# steady_mega_shield_v1_4.net
KiCad netlist of a schematic drawn in EAGLE
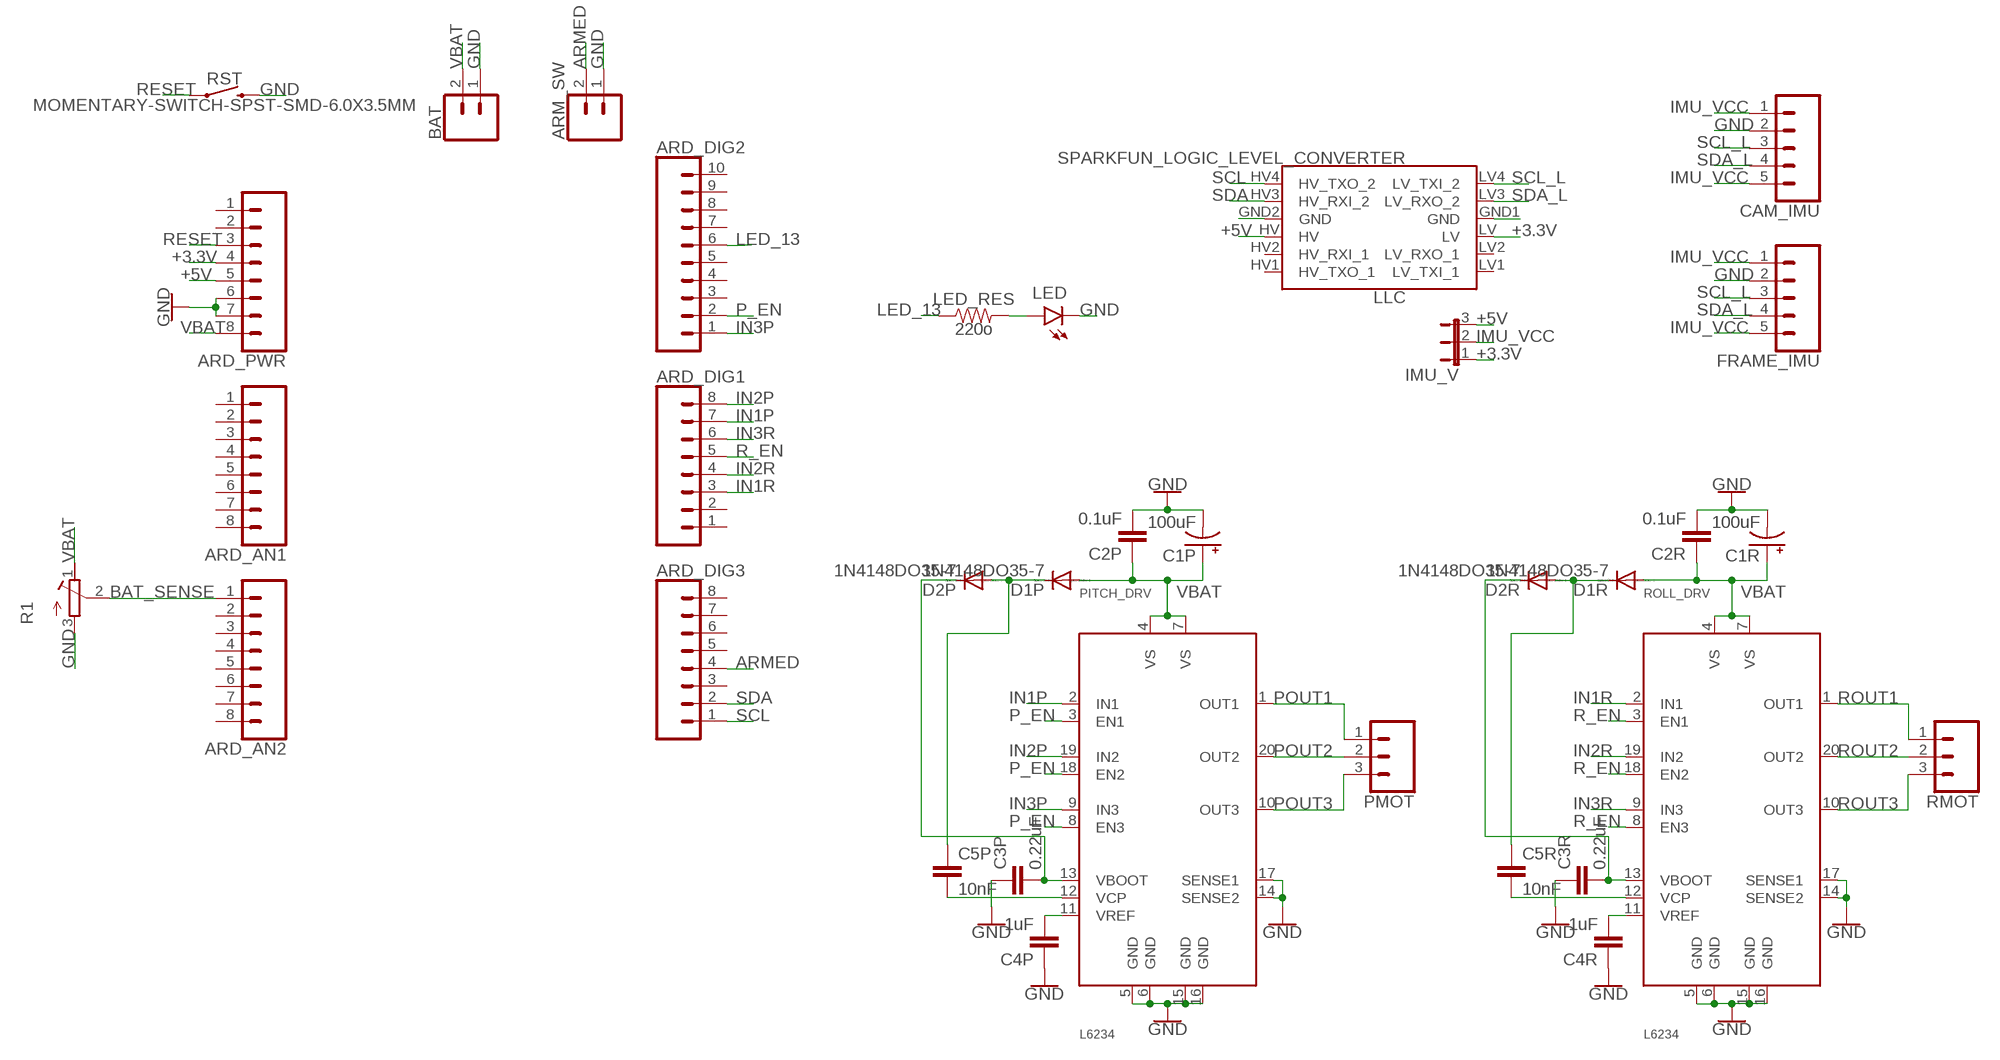
[diagram p0: schematic, sheet 1]

(export (version "E")
  (design (tool "Eeschema 10.0.6"))
  (components
    (comp (ref "ARD_AN1")
      (value "CONN_08\"")
      (footprint "eagle-import:1X08")
      (libsource (lib "eagle-import") (part "CONN_08{dblquote}"))
    )
    (comp (ref "ARD_AN2")
      (value "CONN_08\"")
      (footprint "eagle-import:1X08")
      (libsource (lib "eagle-import") (part "CONN_08{dblquote}"))
    )
    (comp (ref "ARD_DIG1")
      (value "CONN_08\"")
      (footprint "eagle-import:1X08")
      (libsource (lib "eagle-import") (part "CONN_08{dblquote}"))
    )
    (comp (ref "ARD_DIG2")
      (value "CONN_10\"")
      (footprint "eagle-import:1X10")
      (libsource (lib "eagle-import") (part "CONN_10{dblquote}"))
    )
    (comp (ref "ARD_DIG3")
      (value "CONN_08\"")
      (footprint "eagle-import:1X08")
      (libsource (lib "eagle-import") (part "CONN_08{dblquote}"))
    )
    (comp (ref "ARD_PWR")
      (value "CONN_08\"")
      (footprint "eagle-import:1X08")
      (libsource (lib "eagle-import") (part "CONN_08{dblquote}"))
    )
    (comp (ref "ARM_SW")
      (value "CONN_02")
      (footprint "eagle-import:1X02")
      (libsource (lib "eagle-import") (part "CONN_02"))
    )
    (comp (ref "BAT")
      (value "CONN_02")
      (footprint "eagle-import:1X02")
      (libsource (lib "eagle-import") (part "CONN_02"))
    )
    (comp (ref "C1P")
      (value "100uF")
      (footprint "eagle-import:CPOL-RADIAL-2.5MM-6.5MM")
      (libsource (lib "eagle-import") (part "100UF-POLAR-RADIAL-2.5MM-25V-20%"))
    )
    (comp (ref "C1R")
      (value "100uF")
      (footprint "eagle-import:CPOL-RADIAL-2.5MM-6.5MM")
      (libsource (lib "eagle-import") (part "100UF-POLAR-RADIAL-2.5MM-25V-20%"))
    )
    (comp (ref "C2P")
      (value "0.1uF")
      (footprint "eagle-import:C025-024X044")
      (libsource (lib "eagle-import") (part "C-EU025-024X044"))
    )
    (comp (ref "C2R")
      (value "0.1uF")
      (footprint "eagle-import:C025-024X044")
      (libsource (lib "eagle-import") (part "C-EU025-024X044"))
    )
    (comp (ref "C3P")
      (value "0.22uF")
      (footprint "eagle-import:C5B2.5")
      (libsource (lib "eagle-import") (part "C5/2.5"))
    )
    (comp (ref "C3R")
      (value "0.22uF")
      (footprint "eagle-import:C5B2.5")
      (libsource (lib "eagle-import") (part "C5/2.5"))
    )
    (comp (ref "C4P")
      (value "1uF")
      (footprint "eagle-import:C5B5.5")
      (libsource (lib "eagle-import") (part "C5/5.5"))
    )
    (comp (ref "C4R")
      (value "1uF")
      (footprint "eagle-import:C5B5.5")
      (libsource (lib "eagle-import") (part "C5/5.5"))
    )
    (comp (ref "C5P")
      (value "10nF")
      (footprint "eagle-import:C5B2.5")
      (libsource (lib "eagle-import") (part "C5/2.5"))
    )
    (comp (ref "C5R")
      (value "10nF")
      (footprint "eagle-import:C5B2.5")
      (libsource (lib "eagle-import") (part "C5/2.5"))
    )
    (comp (ref "CAM_IMU")
      (value "CONN_05JST")
      (footprint "eagle-import:JST-5-PTH")
      (libsource (lib "eagle-import") (part "CONN_05JST"))
    )
    (comp (ref "D1P")
      (value "1N4148DO35-7")
      (footprint "eagle-import:DO35-7")
      (libsource (lib "eagle-import") (part "1N4148DO35-7"))
    )
    (comp (ref "D1R")
      (value "1N4148DO35-7")
      (footprint "eagle-import:DO35-7")
      (libsource (lib "eagle-import") (part "1N4148DO35-7"))
    )
    (comp (ref "D2P")
      (value "1N4148DO35-7")
      (footprint "eagle-import:DO35-7")
      (libsource (lib "eagle-import") (part "1N4148DO35-7"))
    )
    (comp (ref "D2R")
      (value "1N4148DO35-7")
      (footprint "eagle-import:DO35-7")
      (libsource (lib "eagle-import") (part "1N4148DO35-7"))
    )
    (comp (ref "FRAME_IMU")
      (value "CONN_05JST")
      (footprint "eagle-import:JST-5-PTH")
      (libsource (lib "eagle-import") (part "CONN_05JST"))
    )
    (comp (ref "IMU_V")
      (value "JP2E")
      (footprint "eagle-import:JP2")
      (libsource (lib "eagle-import") (part "JP2E"))
    )
    (comp (ref "LED")
      (value "LED3MM")
      (footprint "eagle-import:LED_3MM")
      (libsource (lib "eagle-import") (part "LED3MM"))
    )
    (comp (ref "LED_RES")
      (value "220o")
      (footprint "eagle-import:0805")
      (libsource (lib "eagle-import") (part "RESISTOR0805"))
    )
    (comp (ref "LLC")
      (value "SPARKFUN_LOGIC_LEVEL_CONVERTER")
      (footprint "eagle-import:SPARKFUN_LOGIC_LEVEL_CONVERTER")
      (libsource (lib "eagle-import") (part "SPARKFUN_LOGIC_LEVEL_CONVERTER"))
    )
    (comp (ref "PITCH_DRV")
      (value "L6234")
      (footprint "eagle-import:DIL20")
      (libsource (lib "eagle-import") (part "L6234"))
    )
    (comp (ref "PMOT")
      (value "CONN_03POLAR")
      (footprint "eagle-import:MOLEX-1X3")
      (libsource (lib "eagle-import") (part "CONN_03POLAR"))
    )
    (comp (ref "R1")
      (value "R-TRIMMT93XB")
      (footprint "eagle-import:RTRIMT93XB")
      (libsource (lib "eagle-import") (part "R-TRIMMT93XB"))
    )
    (comp (ref "RMOT")
      (value "CONN_03POLAR")
      (footprint "eagle-import:MOLEX-1X3")
      (libsource (lib "eagle-import") (part "CONN_03POLAR"))
    )
    (comp (ref "ROLL_DRV")
      (value "L6234")
      (footprint "eagle-import:DIL20")
      (libsource (lib "eagle-import") (part "L6234"))
    )
    (comp (ref "RST")
      (value "MOMENTARY-SWITCH-SPST-SMD-6.0X3.5MM")
      (footprint "eagle-import:TACTILE_SWITCH_SMD_6.0X3.5MM")
      (libsource (lib "eagle-import") (part "MOMENTARY-SWITCH-SPST-SMD-6.0X3.5MM"))
    )
  )
  (nets
    (net (code "1") (name "/+3.3V") (class "Default")
      (node (ref "ARD_PWR") (pin "4") (pinfunction "4_4") (pintype "passive"))
      (node (ref "IMU_V") (pin "1") (pinfunction "1_1") (pintype "passive"))
      (node (ref "LLC") (pin "LV") (pinfunction "LV_LV") (pintype "power_in"))
    )
    (net (code "2") (name "/+5V") (class "Default")
      (node (ref "ARD_PWR") (pin "5") (pinfunction "5_5") (pintype "passive"))
      (node (ref "IMU_V") (pin "3") (pinfunction "3_3") (pintype "passive"))
      (node (ref "LLC") (pin "HV") (pinfunction "HV_HV") (pintype "power_in"))
    )
    (net (code "3") (name "/ARMED") (class "Default")
      (node (ref "ARD_DIG3") (pin "4") (pinfunction "4_4") (pintype "passive"))
      (node (ref "ARM_SW") (pin "2") (pinfunction "2_2") (pintype "passive"))
    )
    (net (code "4") (name "/BAT_SENSE") (class "Default")
      (node (ref "ARD_AN2") (pin "1") (pinfunction "1_1") (pintype "passive"))
      (node (ref "R1") (pin "2") (pinfunction "S_2") (pintype "passive"))
    )
    (net (code "5") (name "/IMU_VCC") (class "Default")
      (node (ref "CAM_IMU") (pin "1") (pinfunction "1_1") (pintype "passive"))
      (node (ref "CAM_IMU") (pin "5") (pinfunction "5_5") (pintype "passive"))
      (node (ref "FRAME_IMU") (pin "1") (pinfunction "1_1") (pintype "passive"))
      (node (ref "FRAME_IMU") (pin "5") (pinfunction "5_5") (pintype "passive"))
      (node (ref "IMU_V") (pin "2") (pinfunction "2_2") (pintype "passive"))
    )
    (net (code "6") (name "/IN1P") (class "Default")
      (node (ref "ARD_DIG1") (pin "7") (pinfunction "7_7") (pintype "passive"))
      (node (ref "PITCH_DRV") (pin "2") (pinfunction "IN1_2") (pintype "bidirectional"))
    )
    (net (code "7") (name "/IN1R") (class "Default")
      (node (ref "ARD_DIG1") (pin "3") (pinfunction "3_3") (pintype "passive"))
      (node (ref "ROLL_DRV") (pin "2") (pinfunction "IN1_2") (pintype "bidirectional"))
    )
    (net (code "8") (name "/IN2P") (class "Default")
      (node (ref "ARD_DIG1") (pin "8") (pinfunction "8_8") (pintype "passive"))
      (node (ref "PITCH_DRV") (pin "19") (pinfunction "IN2_19") (pintype "bidirectional"))
    )
    (net (code "9") (name "/IN2R") (class "Default")
      (node (ref "ARD_DIG1") (pin "4") (pinfunction "4_4") (pintype "passive"))
      (node (ref "ROLL_DRV") (pin "19") (pinfunction "IN2_19") (pintype "bidirectional"))
    )
    (net (code "10") (name "/IN3P") (class "Default")
      (node (ref "ARD_DIG2") (pin "1") (pinfunction "1_1") (pintype "passive"))
      (node (ref "PITCH_DRV") (pin "9") (pinfunction "IN3_9") (pintype "bidirectional"))
    )
    (net (code "11") (name "/IN3R") (class "Default")
      (node (ref "ARD_DIG1") (pin "6") (pinfunction "6_6") (pintype "passive"))
      (node (ref "ROLL_DRV") (pin "9") (pinfunction "IN3_9") (pintype "bidirectional"))
    )
    (net (code "12") (name "/LED_13") (class "Default")
      (node (ref "ARD_DIG2") (pin "6") (pinfunction "6_6") (pintype "passive"))
      (node (ref "LED_RES") (pin "1") (pinfunction "1_1") (pintype "passive"))
    )
    (net (code "13") (name "/POUT1") (class "Default")
      (node (ref "PITCH_DRV") (pin "1") (pinfunction "OUT1_1") (pintype "bidirectional"))
      (node (ref "PMOT") (pin "1") (pinfunction "1_1") (pintype "passive"))
    )
    (net (code "14") (name "/POUT2") (class "Default")
      (node (ref "PITCH_DRV") (pin "20") (pinfunction "OUT2_20") (pintype "bidirectional"))
      (node (ref "PMOT") (pin "2") (pinfunction "2_2") (pintype "passive"))
    )
    (net (code "15") (name "/POUT3") (class "Default")
      (node (ref "PITCH_DRV") (pin "10") (pinfunction "OUT3_10") (pintype "bidirectional"))
      (node (ref "PMOT") (pin "3") (pinfunction "3_3") (pintype "passive"))
    )
    (net (code "16") (name "/P_EN") (class "Default")
      (node (ref "ARD_DIG2") (pin "2") (pinfunction "2_2") (pintype "passive"))
      (node (ref "PITCH_DRV") (pin "18") (pinfunction "EN2_18") (pintype "bidirectional"))
      (node (ref "PITCH_DRV") (pin "3") (pinfunction "EN1_3") (pintype "bidirectional"))
      (node (ref "PITCH_DRV") (pin "8") (pinfunction "EN3_8") (pintype "bidirectional"))
    )
    (net (code "17") (name "/RESET") (class "Default")
      (node (ref "ARD_PWR") (pin "3") (pinfunction "3_3") (pintype "passive"))
      (node (ref "RST") (pin "1") (pinfunction "1_1") (pintype "passive"))
    )
    (net (code "18") (name "/ROUT1") (class "Default")
      (node (ref "RMOT") (pin "1") (pinfunction "1_1") (pintype "passive"))
      (node (ref "ROLL_DRV") (pin "1") (pinfunction "OUT1_1") (pintype "bidirectional"))
    )
    (net (code "19") (name "/ROUT2") (class "Default")
      (node (ref "RMOT") (pin "2") (pinfunction "2_2") (pintype "passive"))
      (node (ref "ROLL_DRV") (pin "20") (pinfunction "OUT2_20") (pintype "bidirectional"))
    )
    (net (code "20") (name "/ROUT3") (class "Default")
      (node (ref "RMOT") (pin "3") (pinfunction "3_3") (pintype "passive"))
      (node (ref "ROLL_DRV") (pin "10") (pinfunction "OUT3_10") (pintype "bidirectional"))
    )
    (net (code "21") (name "/R_EN") (class "Default")
      (node (ref "ARD_DIG1") (pin "5") (pinfunction "5_5") (pintype "passive"))
      (node (ref "ROLL_DRV") (pin "18") (pinfunction "EN2_18") (pintype "bidirectional"))
      (node (ref "ROLL_DRV") (pin "3") (pinfunction "EN1_3") (pintype "bidirectional"))
      (node (ref "ROLL_DRV") (pin "8") (pinfunction "EN3_8") (pintype "bidirectional"))
    )
    (net (code "22") (name "/SCL") (class "Default")
      (node (ref "ARD_DIG3") (pin "1") (pinfunction "1_1") (pintype "passive"))
      (node (ref "LLC") (pin "HV4") (pinfunction "HV_TXO_2_HV4") (pintype "bidirectional"))
    )
    (net (code "23") (name "/SCL_L") (class "Default")
      (node (ref "CAM_IMU") (pin "3") (pinfunction "3_3") (pintype "passive"))
      (node (ref "FRAME_IMU") (pin "3") (pinfunction "3_3") (pintype "passive"))
      (node (ref "LLC") (pin "LV4") (pinfunction "LV_TXI_2_LV4") (pintype "bidirectional"))
    )
    (net (code "24") (name "/SDA") (class "Default")
      (node (ref "ARD_DIG3") (pin "2") (pinfunction "2_2") (pintype "passive"))
      (node (ref "LLC") (pin "HV3") (pinfunction "HV_RXI_2_HV3") (pintype "bidirectional"))
    )
    (net (code "25") (name "/SDA_L") (class "Default")
      (node (ref "CAM_IMU") (pin "4") (pinfunction "4_4") (pintype "passive"))
      (node (ref "FRAME_IMU") (pin "4") (pinfunction "4_4") (pintype "passive"))
      (node (ref "LLC") (pin "LV3") (pinfunction "LV_RXO_2_LV3") (pintype "bidirectional"))
    )
    (net (code "26") (name "/VBAT") (class "Default")
      (node (ref "ARD_PWR") (pin "8") (pinfunction "8_8") (pintype "passive"))
      (node (ref "BAT") (pin "2") (pinfunction "2_2") (pintype "passive"))
      (node (ref "C1P") (pin "1") (pinfunction "+_1") (pintype "passive"))
      (node (ref "C1R") (pin "1") (pinfunction "+_1") (pintype "passive"))
      (node (ref "C2P") (pin "1") (pinfunction "1_1") (pintype "passive"))
      (node (ref "C2R") (pin "1") (pinfunction "1_1") (pintype "passive"))
      (node (ref "D1P") (pin "A") (pinfunction "A_A") (pintype "passive"))
      (node (ref "D1R") (pin "A") (pinfunction "A_A") (pintype "passive"))
      (node (ref "PITCH_DRV") (pin "4") (pinfunction "VS_4") (pintype "bidirectional"))
      (node (ref "PITCH_DRV") (pin "7") (pinfunction "VS_7") (pintype "bidirectional"))
      (node (ref "R1") (pin "1") (pinfunction "E_1") (pintype "passive"))
      (node (ref "ROLL_DRV") (pin "4") (pinfunction "VS_4") (pintype "bidirectional"))
      (node (ref "ROLL_DRV") (pin "7") (pinfunction "VS_7") (pintype "bidirectional"))
    )
    (net (code "27") (name "GND") (class "Default")
      (node (ref "ARD_PWR") (pin "6") (pinfunction "6_6") (pintype "passive"))
      (node (ref "ARD_PWR") (pin "7") (pinfunction "7_7") (pintype "passive"))
      (node (ref "ARM_SW") (pin "1") (pinfunction "1_1") (pintype "passive"))
      (node (ref "BAT") (pin "1") (pinfunction "1_1") (pintype "passive"))
      (node (ref "C1P") (pin "2") (pinfunction "-_2") (pintype "passive"))
      (node (ref "C1R") (pin "2") (pinfunction "-_2") (pintype "passive"))
      (node (ref "C2P") (pin "2") (pinfunction "2_2") (pintype "passive"))
      (node (ref "C2R") (pin "2") (pinfunction "2_2") (pintype "passive"))
      (node (ref "C3P") (pin "1") (pinfunction "1_1") (pintype "passive"))
      (node (ref "C3R") (pin "1") (pinfunction "1_1") (pintype "passive"))
      (node (ref "C4P") (pin "1") (pinfunction "1_1") (pintype "passive"))
      (node (ref "C4R") (pin "1") (pinfunction "1_1") (pintype "passive"))
      (node (ref "CAM_IMU") (pin "2") (pinfunction "2_2") (pintype "passive"))
      (node (ref "FRAME_IMU") (pin "2") (pinfunction "2_2") (pintype "passive"))
      (node (ref "LED") (pin "K") (pinfunction "C_K") (pintype "passive"))
      (node (ref "LLC") (pin "GND1") (pinfunction "GND_GND1") (pintype "power_in"))
      (node (ref "LLC") (pin "GND2") (pinfunction "GND_GND2") (pintype "power_in"))
      (node (ref "PITCH_DRV") (pin "14") (pinfunction "SENSE2_14") (pintype "bidirectional"))
      (node (ref "PITCH_DRV") (pin "15") (pinfunction "GND_15") (pintype "bidirectional"))
      (node (ref "PITCH_DRV") (pin "16") (pinfunction "GND_16") (pintype "bidirectional"))
      (node (ref "PITCH_DRV") (pin "17") (pinfunction "SENSE1_17") (pintype "bidirectional"))
      (node (ref "PITCH_DRV") (pin "5") (pinfunction "GND_5") (pintype "bidirectional"))
      (node (ref "PITCH_DRV") (pin "6") (pinfunction "GND_6") (pintype "bidirectional"))
      (node (ref "R1") (pin "3") (pinfunction "A_3") (pintype "passive"))
      (node (ref "ROLL_DRV") (pin "14") (pinfunction "SENSE2_14") (pintype "bidirectional"))
      (node (ref "ROLL_DRV") (pin "15") (pinfunction "GND_15") (pintype "bidirectional"))
      (node (ref "ROLL_DRV") (pin "16") (pinfunction "GND_16") (pintype "bidirectional"))
      (node (ref "ROLL_DRV") (pin "17") (pinfunction "SENSE1_17") (pintype "bidirectional"))
      (node (ref "ROLL_DRV") (pin "5") (pinfunction "GND_5") (pintype "bidirectional"))
      (node (ref "ROLL_DRV") (pin "6") (pinfunction "GND_6") (pintype "bidirectional"))
      (node (ref "RST") (pin "2") (pinfunction "2_2") (pintype "passive"))
    )
    (net (code "28") (name "Net-(C5P-Pad1)") (class "Default")
      (node (ref "C5P") (pin "1") (pinfunction "1_1") (pintype "passive"))
      (node (ref "D1P") (pin "C") (pinfunction "C_C") (pintype "passive"))
      (node (ref "D2P") (pin "A") (pinfunction "A_A") (pintype "passive"))
    )
    (net (code "29") (name "Net-(C5R-Pad1)") (class "Default")
      (node (ref "C5R") (pin "1") (pinfunction "1_1") (pintype "passive"))
      (node (ref "D1R") (pin "C") (pinfunction "C_C") (pintype "passive"))
      (node (ref "D2R") (pin "A") (pinfunction "A_A") (pintype "passive"))
    )
    (net (code "30") (name "Net-(LED-PadA)") (class "Default")
      (node (ref "LED") (pin "A") (pinfunction "A_A") (pintype "passive"))
      (node (ref "LED_RES") (pin "2") (pinfunction "2_2") (pintype "passive"))
    )
    (net (code "31") (name "Net-(PITCH_DRV-VBOOT)") (class "Default")
      (node (ref "C3P") (pin "2") (pinfunction "2_2") (pintype "passive"))
      (node (ref "D2P") (pin "C") (pinfunction "C_C") (pintype "passive"))
      (node (ref "PITCH_DRV") (pin "13") (pinfunction "VBOOT_13") (pintype "bidirectional"))
    )
    (net (code "32") (name "Net-(PITCH_DRV-VCP)") (class "Default")
      (node (ref "C5P") (pin "2") (pinfunction "2_2") (pintype "passive"))
      (node (ref "PITCH_DRV") (pin "12") (pinfunction "VCP_12") (pintype "bidirectional"))
    )
    (net (code "33") (name "Net-(PITCH_DRV-VREF)") (class "Default")
      (node (ref "C4P") (pin "2") (pinfunction "2_2") (pintype "passive"))
      (node (ref "PITCH_DRV") (pin "11") (pinfunction "VREF_11") (pintype "bidirectional"))
    )
    (net (code "34") (name "Net-(ROLL_DRV-VBOOT)") (class "Default")
      (node (ref "C3R") (pin "2") (pinfunction "2_2") (pintype "passive"))
      (node (ref "D2R") (pin "C") (pinfunction "C_C") (pintype "passive"))
      (node (ref "ROLL_DRV") (pin "13") (pinfunction "VBOOT_13") (pintype "bidirectional"))
    )
    (net (code "35") (name "Net-(ROLL_DRV-VCP)") (class "Default")
      (node (ref "C5R") (pin "2") (pinfunction "2_2") (pintype "passive"))
      (node (ref "ROLL_DRV") (pin "12") (pinfunction "VCP_12") (pintype "bidirectional"))
    )
    (net (code "36") (name "Net-(ROLL_DRV-VREF)") (class "Default")
      (node (ref "C4R") (pin "2") (pinfunction "2_2") (pintype "passive"))
      (node (ref "ROLL_DRV") (pin "11") (pinfunction "VREF_11") (pintype "bidirectional"))
    )
    (net (code "37") (name "unconnected-(ARD_AN1-Pad1)") (class "Default")
      (node (ref "ARD_AN1") (pin "1") (pinfunction "1_1") (pintype "passive"))
    )
    (net (code "38") (name "unconnected-(ARD_AN1-Pad2)") (class "Default")
      (node (ref "ARD_AN1") (pin "2") (pinfunction "2_2") (pintype "passive"))
    )
    (net (code "39") (name "unconnected-(ARD_AN1-Pad3)") (class "Default")
      (node (ref "ARD_AN1") (pin "3") (pinfunction "3_3") (pintype "passive"))
    )
    (net (code "40") (name "unconnected-(ARD_AN1-Pad4)") (class "Default")
      (node (ref "ARD_AN1") (pin "4") (pinfunction "4_4") (pintype "passive"))
    )
    (net (code "41") (name "unconnected-(ARD_AN1-Pad5)") (class "Default")
      (node (ref "ARD_AN1") (pin "5") (pinfunction "5_5") (pintype "passive"))
    )
    (net (code "42") (name "unconnected-(ARD_AN1-Pad6)") (class "Default")
      (node (ref "ARD_AN1") (pin "6") (pinfunction "6_6") (pintype "passive"))
    )
    (net (code "43") (name "unconnected-(ARD_AN1-Pad7)") (class "Default")
      (node (ref "ARD_AN1") (pin "7") (pinfunction "7_7") (pintype "passive"))
    )
    (net (code "44") (name "unconnected-(ARD_AN1-Pad8)") (class "Default")
      (node (ref "ARD_AN1") (pin "8") (pinfunction "8_8") (pintype "passive"))
    )
    (net (code "45") (name "unconnected-(ARD_AN2-Pad2)") (class "Default")
      (node (ref "ARD_AN2") (pin "2") (pinfunction "2_2") (pintype "passive"))
    )
    (net (code "46") (name "unconnected-(ARD_AN2-Pad3)") (class "Default")
      (node (ref "ARD_AN2") (pin "3") (pinfunction "3_3") (pintype "passive"))
    )
    (net (code "47") (name "unconnected-(ARD_AN2-Pad4)") (class "Default")
      (node (ref "ARD_AN2") (pin "4") (pinfunction "4_4") (pintype "passive"))
    )
    (net (code "48") (name "unconnected-(ARD_AN2-Pad5)") (class "Default")
      (node (ref "ARD_AN2") (pin "5") (pinfunction "5_5") (pintype "passive"))
    )
    (net (code "49") (name "unconnected-(ARD_AN2-Pad6)") (class "Default")
      (node (ref "ARD_AN2") (pin "6") (pinfunction "6_6") (pintype "passive"))
    )
    (net (code "50") (name "unconnected-(ARD_AN2-Pad7)") (class "Default")
      (node (ref "ARD_AN2") (pin "7") (pinfunction "7_7") (pintype "passive"))
    )
    (net (code "51") (name "unconnected-(ARD_AN2-Pad8)") (class "Default")
      (node (ref "ARD_AN2") (pin "8") (pinfunction "8_8") (pintype "passive"))
    )
    (net (code "52") (name "unconnected-(ARD_DIG1-Pad1)") (class "Default")
      (node (ref "ARD_DIG1") (pin "1") (pinfunction "1_1") (pintype "passive"))
    )
    (net (code "53") (name "unconnected-(ARD_DIG1-Pad2)") (class "Default")
      (node (ref "ARD_DIG1") (pin "2") (pinfunction "2_2") (pintype "passive"))
    )
    (net (code "54") (name "unconnected-(ARD_DIG2-Pad3)") (class "Default")
      (node (ref "ARD_DIG2") (pin "3") (pinfunction "3_3") (pintype "passive"))
    )
    (net (code "55") (name "unconnected-(ARD_DIG2-Pad4)") (class "Default")
      (node (ref "ARD_DIG2") (pin "4") (pinfunction "4_4") (pintype "passive"))
    )
    (net (code "56") (name "unconnected-(ARD_DIG2-Pad5)") (class "Default")
      (node (ref "ARD_DIG2") (pin "5") (pinfunction "5_5") (pintype "passive"))
    )
    (net (code "57") (name "unconnected-(ARD_DIG2-Pad7)") (class "Default")
      (node (ref "ARD_DIG2") (pin "7") (pinfunction "7_7") (pintype "passive"))
    )
    (net (code "58") (name "unconnected-(ARD_DIG2-Pad8)") (class "Default")
      (node (ref "ARD_DIG2") (pin "8") (pinfunction "8_8") (pintype "passive"))
    )
    (net (code "59") (name "unconnected-(ARD_DIG2-Pad9)") (class "Default")
      (node (ref "ARD_DIG2") (pin "9") (pinfunction "9_9") (pintype "passive"))
    )
    (net (code "60") (name "unconnected-(ARD_DIG2-Pad10)") (class "Default")
      (node (ref "ARD_DIG2") (pin "10") (pinfunction "10_10") (pintype "passive"))
    )
    (net (code "61") (name "unconnected-(ARD_DIG3-Pad3)") (class "Default")
      (node (ref "ARD_DIG3") (pin "3") (pinfunction "3_3") (pintype "passive"))
    )
    (net (code "62") (name "unconnected-(ARD_DIG3-Pad5)") (class "Default")
      (node (ref "ARD_DIG3") (pin "5") (pinfunction "5_5") (pintype "passive"))
    )
    (net (code "63") (name "unconnected-(ARD_DIG3-Pad6)") (class "Default")
      (node (ref "ARD_DIG3") (pin "6") (pinfunction "6_6") (pintype "passive"))
    )
    (net (code "64") (name "unconnected-(ARD_DIG3-Pad7)") (class "Default")
      (node (ref "ARD_DIG3") (pin "7") (pinfunction "7_7") (pintype "passive"))
    )
    (net (code "65") (name "unconnected-(ARD_DIG3-Pad8)") (class "Default")
      (node (ref "ARD_DIG3") (pin "8") (pinfunction "8_8") (pintype "passive"))
    )
    (net (code "66") (name "unconnected-(ARD_PWR-Pad1)") (class "Default")
      (node (ref "ARD_PWR") (pin "1") (pinfunction "1_1") (pintype "passive"))
    )
    (net (code "67") (name "unconnected-(ARD_PWR-Pad2)") (class "Default")
      (node (ref "ARD_PWR") (pin "2") (pinfunction "2_2") (pintype "passive"))
    )
    (net (code "68") (name "unconnected-(LLC-HV_RXI_1-PadHV2)") (class "Default")
      (node (ref "LLC") (pin "HV2") (pinfunction "HV_RXI_1_HV2") (pintype "bidirectional"))
    )
    (net (code "69") (name "unconnected-(LLC-HV_TXO_1-PadHV1)") (class "Default")
      (node (ref "LLC") (pin "HV1") (pinfunction "HV_TXO_1_HV1") (pintype "bidirectional"))
    )
    (net (code "70") (name "unconnected-(LLC-LV_RXO_1-PadLV2)") (class "Default")
      (node (ref "LLC") (pin "LV2") (pinfunction "LV_RXO_1_LV2") (pintype "bidirectional"))
    )
    (net (code "71") (name "unconnected-(LLC-LV_TXI_1-PadLV1)") (class "Default")
      (node (ref "LLC") (pin "LV1") (pinfunction "LV_TXI_1_LV1") (pintype "bidirectional"))
    )
  )
)
